# 605_motor.net
KiCad netlist of a schematic drawn in EAGLE
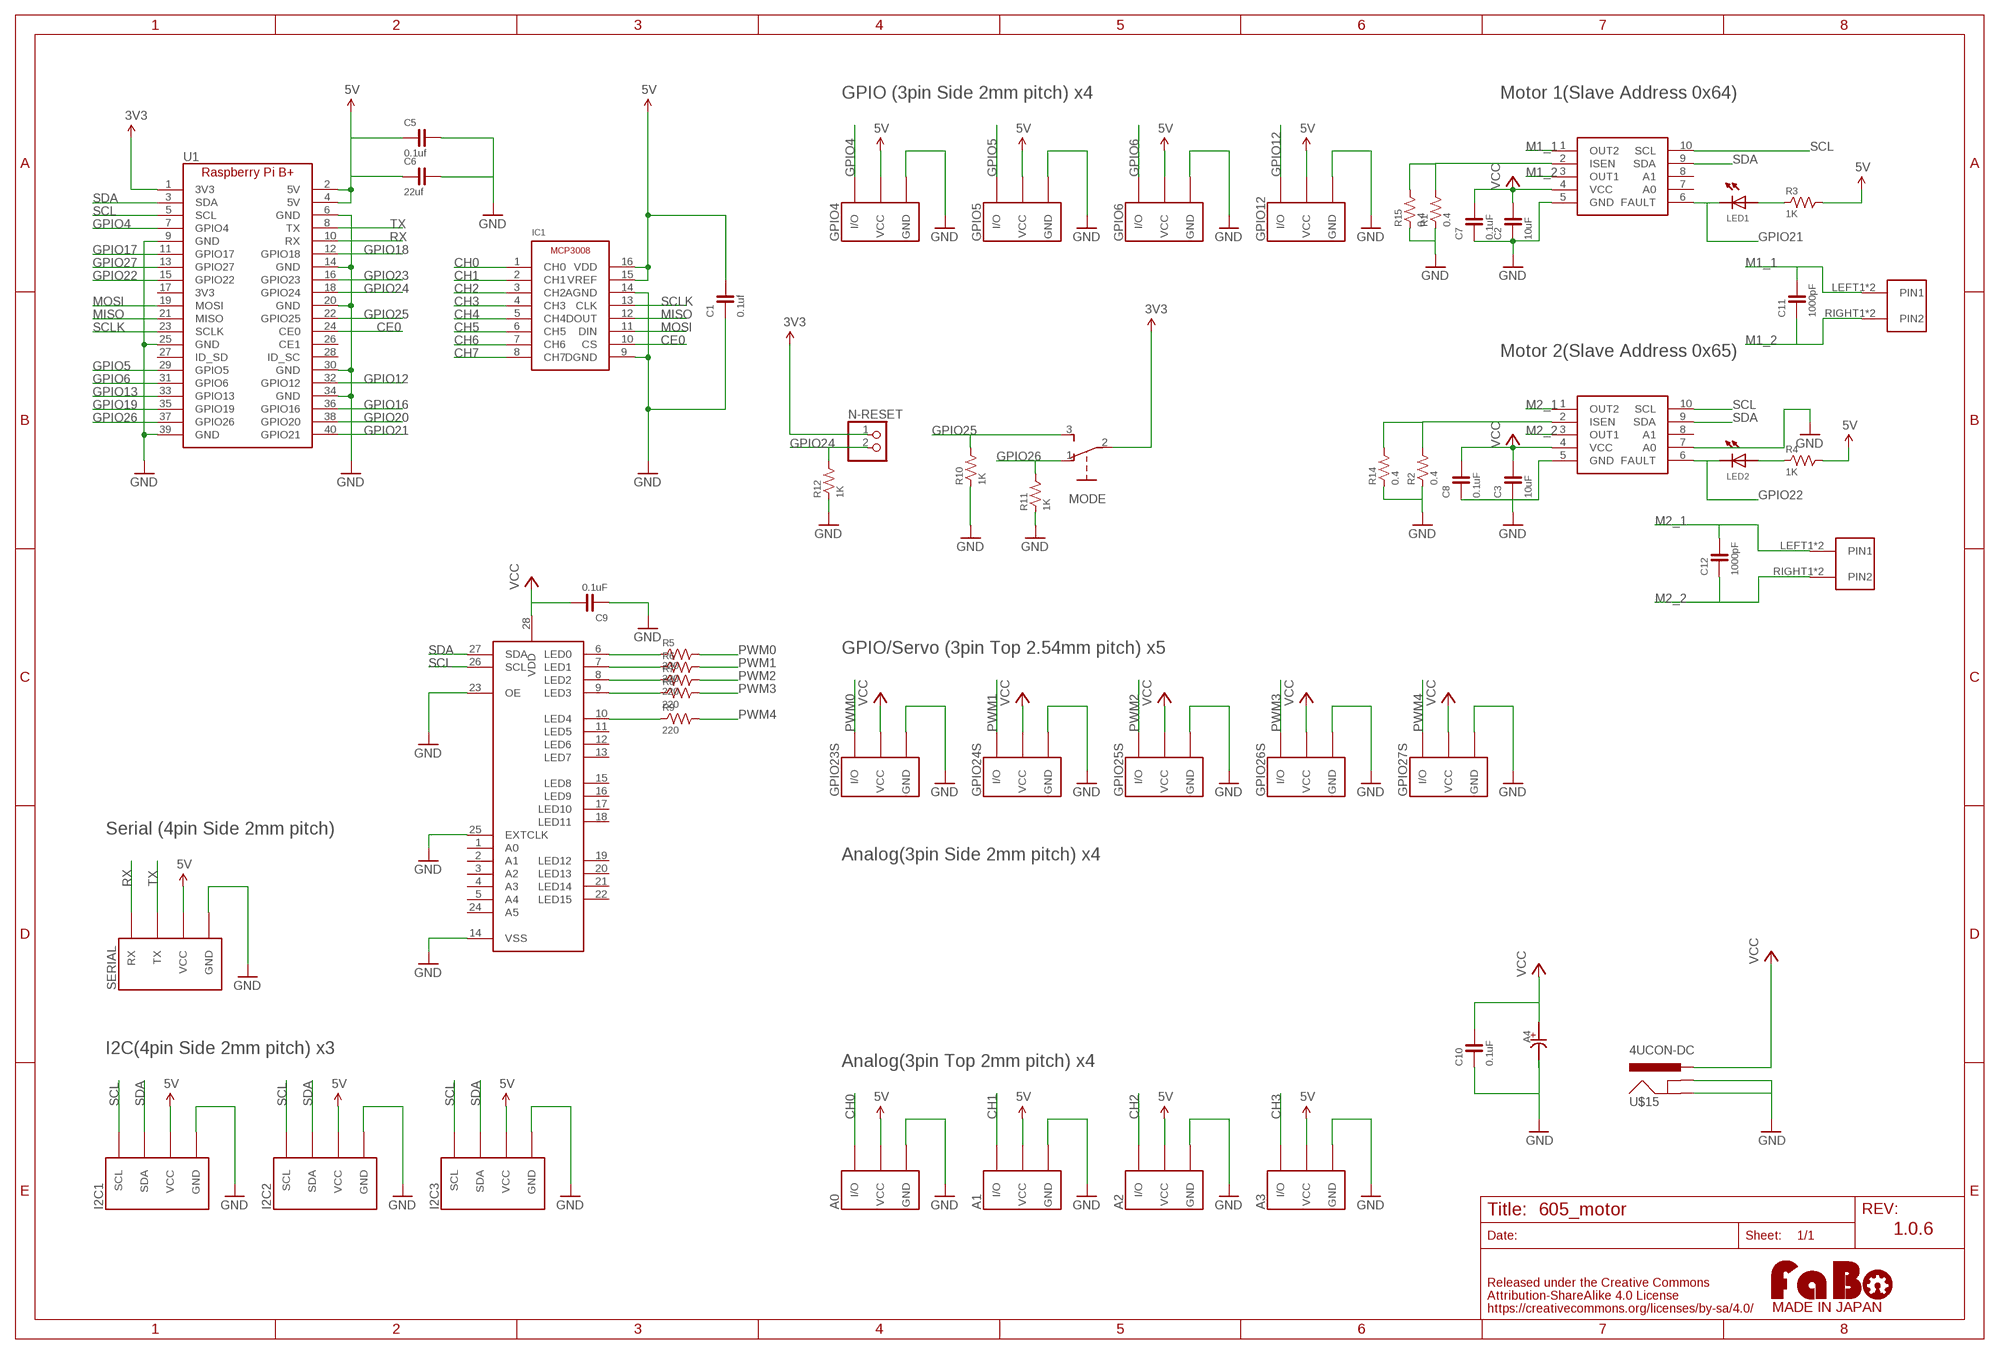
[diagram p0: schematic, sheet 1]

(export (version "E")
  (design (tool "Eeschema 10.0.6"))
  (components
    (comp (ref "A0")
      (value "FABO_BRICK_3PIN-B03B-PASK-1")
      (footprint "eagle-import:FABO_BRICK_3PIN_B03B-PASK-1")
      (libsource (lib "eagle-import") (part "FABO_BRICK_3PIN-B03B-PASK-1"))
    )
    (comp (ref "A1")
      (value "FABO_BRICK_3PIN-B03B-PASK-1")
      (footprint "eagle-import:FABO_BRICK_3PIN_B03B-PASK-1")
      (libsource (lib "eagle-import") (part "FABO_BRICK_3PIN-B03B-PASK-1"))
    )
    (comp (ref "A2")
      (value "FABO_BRICK_3PIN-B03B-PASK-1")
      (footprint "eagle-import:FABO_BRICK_3PIN_B03B-PASK-1")
      (libsource (lib "eagle-import") (part "FABO_BRICK_3PIN-B03B-PASK-1"))
    )
    (comp (ref "A3")
      (value "FABO_BRICK_3PIN-B03B-PASK-1")
      (footprint "eagle-import:FABO_BRICK_3PIN_B03B-PASK-1")
      (libsource (lib "eagle-import") (part "FABO_BRICK_3PIN-B03B-PASK-1"))
    )
    (comp (ref "A4")
      (value "CAPACITOR-ALUMIN")
      (footprint "eagle-import:H13")
      (libsource (lib "eagle-import") (part "CAPACITOR-ALUMIN"))
    )
    (comp (ref "C1")
      (value "0.1uf")
      (footprint "eagle-import:0603")
      (libsource (lib "eagle-import") (part "CAPACITOR-0603"))
    )
    (comp (ref "C2")
      (value "10uF")
      (footprint "eagle-import:0603")
      (libsource (lib "eagle-import") (part "CAPACITOR-0603"))
    )
    (comp (ref "C3")
      (value "10uF")
      (footprint "eagle-import:0603")
      (libsource (lib "eagle-import") (part "CAPACITOR-0603"))
    )
    (comp (ref "C5")
      (value "0.1uf")
      (footprint "eagle-import:0603")
      (libsource (lib "eagle-import") (part "CAPACITOR-0603"))
    )
    (comp (ref "C6")
      (value "22uf")
      (footprint "eagle-import:0603")
      (libsource (lib "eagle-import") (part "CAPACITOR-0603"))
    )
    (comp (ref "C7")
      (value "0.1uF")
      (footprint "eagle-import:0603")
      (libsource (lib "eagle-import") (part "CAPACITOR-0603"))
    )
    (comp (ref "C8")
      (value "0.1uF")
      (footprint "eagle-import:0603")
      (libsource (lib "eagle-import") (part "CAPACITOR-0603"))
    )
    (comp (ref "C9")
      (value "0.1uF")
      (footprint "eagle-import:0603")
      (libsource (lib "eagle-import") (part "CAPACITOR-0603"))
    )
    (comp (ref "C10")
      (value "0.1uF")
      (footprint "eagle-import:0603")
      (libsource (lib "eagle-import") (part "CAPACITOR-0603"))
    )
    (comp (ref "C11")
      (value "1000pF")
      (footprint "eagle-import:0603")
      (libsource (lib "eagle-import") (part "CAPACITOR-0603"))
    )
    (comp (ref "C12")
      (value "1000pF")
      (footprint "eagle-import:0603")
      (libsource (lib "eagle-import") (part "CAPACITOR-0603"))
    )
    (comp (ref "GPIO4")
      (value "FABO_BRICK_3PIN-S03B-PASK-2")
      (footprint "eagle-import:FABO_BRICK_3PIN_S03B-PASK-2")
      (libsource (lib "eagle-import") (part "FABO_BRICK_3PIN-S03B-PASK-2"))
    )
    (comp (ref "GPIO5")
      (value "FABO_BRICK_3PIN-S03B-PASK-2")
      (footprint "eagle-import:FABO_BRICK_3PIN_S03B-PASK-2")
      (libsource (lib "eagle-import") (part "FABO_BRICK_3PIN-S03B-PASK-2"))
    )
    (comp (ref "GPIO6")
      (value "FABO_BRICK_3PIN-S03B-PASK-2")
      (footprint "eagle-import:FABO_BRICK_3PIN_S03B-PASK-2")
      (libsource (lib "eagle-import") (part "FABO_BRICK_3PIN-S03B-PASK-2"))
    )
    (comp (ref "GPIO12")
      (value "FABO_BRICK_3PIN-S03B-PASK-2")
      (footprint "eagle-import:FABO_BRICK_3PIN_S03B-PASK-2")
      (libsource (lib "eagle-import") (part "FABO_BRICK_3PIN-S03B-PASK-2"))
    )
    (comp (ref "GPIO23S")
      (value "FABO_BRICK_3PIN-HEADER")
      (footprint "eagle-import:FABO_BRICK_3PIN_HEADER")
      (libsource (lib "eagle-import") (part "FABO_BRICK_3PIN-HEADER"))
    )
    (comp (ref "GPIO24S")
      (value "FABO_BRICK_3PIN-HEADER")
      (footprint "eagle-import:FABO_BRICK_3PIN_HEADER")
      (libsource (lib "eagle-import") (part "FABO_BRICK_3PIN-HEADER"))
    )
    (comp (ref "GPIO25S")
      (value "FABO_BRICK_3PIN-HEADER")
      (footprint "eagle-import:FABO_BRICK_3PIN_HEADER")
      (libsource (lib "eagle-import") (part "FABO_BRICK_3PIN-HEADER"))
    )
    (comp (ref "GPIO26S")
      (value "FABO_BRICK_3PIN-HEADER")
      (footprint "eagle-import:FABO_BRICK_3PIN_HEADER")
      (libsource (lib "eagle-import") (part "FABO_BRICK_3PIN-HEADER"))
    )
    (comp (ref "GPIO27S")
      (value "FABO_BRICK_3PIN-HEADER")
      (footprint "eagle-import:FABO_BRICK_3PIN_HEADER")
      (libsource (lib "eagle-import") (part "FABO_BRICK_3PIN-HEADER"))
    )
    (comp (ref "I2C1")
      (value "FABO_BRICK_I2C-S04B-PASK-2")
      (footprint "eagle-import:FABO_BRICK_I2C_S04B-PASK-2")
      (libsource (lib "eagle-import") (part "FABO_BRICK_I2C-S04B-PASK-2"))
    )
    (comp (ref "I2C2")
      (value "FABO_BRICK_I2C-S04B-PASK-2")
      (footprint "eagle-import:FABO_BRICK_I2C_S04B-PASK-2")
      (libsource (lib "eagle-import") (part "FABO_BRICK_I2C-S04B-PASK-2"))
    )
    (comp (ref "I2C3")
      (value "FABO_BRICK_I2C-S04B-PASK-2")
      (footprint "eagle-import:FABO_BRICK_I2C_S04B-PASK-2")
      (libsource (lib "eagle-import") (part "FABO_BRICK_I2C-S04B-PASK-2"))
    )
    (comp (ref "IC1")
      (value "MICROCHIP-MCP3008")
      (footprint "eagle-import:MICROCHIP-MCP3008")
      (libsource (lib "eagle-import") (part "MICROCHIP-MCP3008"))
    )
    (comp (ref "LED1")
      (value "LED-0603")
      (footprint "eagle-import:0603")
      (libsource (lib "eagle-import") (part "LED-0603"))
    )
    (comp (ref "LED2")
      (value "LED-0603")
      (footprint "eagle-import:0603")
      (libsource (lib "eagle-import") (part "LED-0603"))
    )
    (comp (ref "MODE")
      (value "SLIDE-EG1218")
      (footprint "eagle-import:EG1218")
      (libsource (lib "eagle-import") (part "SLIDE-EG1218"))
    )
    (comp (ref "N-RESET")
      (value "PINHD-1X2")
      (footprint "eagle-import:1X02")
      (libsource (lib "eagle-import") (part "PINHD-1X2"))
    )
    (comp (ref "R1")
      (value "0.4")
      (footprint "eagle-import:0603")
      (libsource (lib "eagle-import") (part "RESISTOR-0603"))
    )
    (comp (ref "R2")
      (value "0.4")
      (footprint "eagle-import:0603")
      (libsource (lib "eagle-import") (part "RESISTOR-0603"))
    )
    (comp (ref "R3")
      (value "1K")
      (footprint "eagle-import:0603")
      (libsource (lib "eagle-import") (part "RESISTOR-0603"))
    )
    (comp (ref "R4")
      (value "1K")
      (footprint "eagle-import:0603")
      (libsource (lib "eagle-import") (part "RESISTOR-0603"))
    )
    (comp (ref "R5")
      (value "220")
      (footprint "eagle-import:0603")
      (libsource (lib "eagle-import") (part "RESISTOR-0603"))
    )
    (comp (ref "R6")
      (value "220")
      (footprint "eagle-import:0603")
      (libsource (lib "eagle-import") (part "RESISTOR-0603"))
    )
    (comp (ref "R7")
      (value "220")
      (footprint "eagle-import:0603")
      (libsource (lib "eagle-import") (part "RESISTOR-0603"))
    )
    (comp (ref "R8")
      (value "220")
      (footprint "eagle-import:0603")
      (libsource (lib "eagle-import") (part "RESISTOR-0603"))
    )
    (comp (ref "R9")
      (value "220")
      (footprint "eagle-import:0603")
      (libsource (lib "eagle-import") (part "RESISTOR-0603"))
    )
    (comp (ref "R10")
      (value "1K")
      (footprint "eagle-import:0603")
      (libsource (lib "eagle-import") (part "RESISTOR-0603"))
    )
    (comp (ref "R11")
      (value "1K")
      (footprint "eagle-import:0603")
      (libsource (lib "eagle-import") (part "RESISTOR-0603"))
    )
    (comp (ref "R12")
      (value "1K")
      (footprint "eagle-import:0603")
      (libsource (lib "eagle-import") (part "RESISTOR-0603"))
    )
    (comp (ref "R14")
      (value "0.4")
      (footprint "eagle-import:0603")
      (libsource (lib "eagle-import") (part "RESISTOR-0603"))
    )
    (comp (ref "R15")
      (value "0.4")
      (footprint "eagle-import:0603")
      (libsource (lib "eagle-import") (part "RESISTOR-0603"))
    )
    (comp (ref "SERIAL")
      (value "FABO_BRICK_SERIAL-S04B-PASK-2")
      (footprint "eagle-import:FABO_BRICK_SERIAL_S04B-PASK-2")
      (libsource (lib "eagle-import") (part "FABO_BRICK_SERIAL-S04B-PASK-2"))
    )
    (comp (ref "U$8")
      (value "DRV8830")
      (footprint "eagle-import:DRV8830")
      (libsource (lib "eagle-import") (part "DRV8830"))
    )
    (comp (ref "U$9")
      (value "PCA9685")
      (footprint "eagle-import:PCA9685")
      (libsource (lib "eagle-import") (part "PCA9685"))
    )
    (comp (ref "U$10")
      (value "DRV8830")
      (footprint "eagle-import:DRV8830")
      (libsource (lib "eagle-import") (part "DRV8830"))
    )
    (comp (ref "U$12")
      (value "ML-1400-S1")
      (footprint "eagle-import:ML-1400-S1")
      (libsource (lib "eagle-import") (part "ML-1400-S1"))
    )
    (comp (ref "U$13")
      (value "ML-1400-S1")
      (footprint "eagle-import:ML-1400-S1")
      (libsource (lib "eagle-import") (part "ML-1400-S1"))
    )
    (comp (ref "U$14")
      (value "LOGO_FABO-M")
      (footprint "eagle-import:LOGO_FABO_MS")
      (libsource (lib "eagle-import") (part "LOGO_FABO-M"))
    )
    (comp (ref "U$15")
      (value "4UCON-DC")
      (footprint "eagle-import:4UCON-DC")
      (libsource (lib "eagle-import") (part "4UCON-DC"))
    )
    (comp (ref "U1")
      (value "RASPBERRY_PI_B+")
      (footprint "eagle-import:RASPBERRY_PI_B+")
      (libsource (lib "eagle-import") (part "RASPBERRY_PI_B+"))
    )
  )
  (nets
    (net (code "1") (name "/CE0") (class "Default")
      (node (ref "IC1") (pin "10") (pinfunction "CS_10") (pintype "bidirectional"))
      (node (ref "U1") (pin "24") (pinfunction "CE0_24") (pintype "bidirectional"))
    )
    (net (code "2") (name "/CH0") (class "Default")
      (node (ref "A0") (pin "I/O") (pinfunction "I/O_I/O") (pintype "bidirectional"))
      (node (ref "IC1") (pin "1") (pinfunction "CH0_1") (pintype "bidirectional"))
    )
    (net (code "3") (name "/CH1") (class "Default")
      (node (ref "A1") (pin "I/O") (pinfunction "I/O_I/O") (pintype "bidirectional"))
      (node (ref "IC1") (pin "2") (pinfunction "CH1_2") (pintype "bidirectional"))
    )
    (net (code "4") (name "/CH2") (class "Default")
      (node (ref "A2") (pin "I/O") (pinfunction "I/O_I/O") (pintype "bidirectional"))
      (node (ref "IC1") (pin "3") (pinfunction "CH2_3") (pintype "bidirectional"))
    )
    (net (code "5") (name "/CH3") (class "Default")
      (node (ref "A3") (pin "I/O") (pinfunction "I/O_I/O") (pintype "bidirectional"))
      (node (ref "IC1") (pin "4") (pinfunction "CH3_4") (pintype "bidirectional"))
    )
    (net (code "6") (name "/CH4") (class "Default")
      (node (ref "IC1") (pin "5") (pinfunction "CH4_5") (pintype "bidirectional"))
    )
    (net (code "7") (name "/CH5") (class "Default")
      (node (ref "IC1") (pin "6") (pinfunction "CH5_6") (pintype "bidirectional"))
    )
    (net (code "8") (name "/CH6") (class "Default")
      (node (ref "IC1") (pin "7") (pinfunction "CH6_7") (pintype "bidirectional"))
    )
    (net (code "9") (name "/CH7") (class "Default")
      (node (ref "IC1") (pin "8") (pinfunction "CH7_8") (pintype "bidirectional"))
    )
    (net (code "10") (name "/GPIO4") (class "Default")
      (node (ref "GPIO4") (pin "I/O") (pinfunction "I/O_I/O") (pintype "bidirectional"))
      (node (ref "U1") (pin "7") (pinfunction "GPIO4_7") (pintype "bidirectional"))
    )
    (net (code "11") (name "/GPIO5") (class "Default")
      (node (ref "GPIO5") (pin "I/O") (pinfunction "I/O_I/O") (pintype "bidirectional"))
      (node (ref "U1") (pin "29") (pinfunction "GPIO5_29") (pintype "bidirectional"))
    )
    (net (code "12") (name "/GPIO6") (class "Default")
      (node (ref "GPIO6") (pin "I/O") (pinfunction "I/O_I/O") (pintype "bidirectional"))
      (node (ref "U1") (pin "31") (pinfunction "GPIO6_31") (pintype "bidirectional"))
    )
    (net (code "13") (name "/GPIO12") (class "Default")
      (node (ref "GPIO12") (pin "I/O") (pinfunction "I/O_I/O") (pintype "bidirectional"))
      (node (ref "U1") (pin "32") (pinfunction "GPIO12_32") (pintype "bidirectional"))
    )
    (net (code "14") (name "/GPIO13") (class "Default")
      (node (ref "U1") (pin "33") (pinfunction "GPIO13_33") (pintype "bidirectional"))
    )
    (net (code "15") (name "/GPIO16") (class "Default")
      (node (ref "U1") (pin "36") (pinfunction "GPIO16_36") (pintype "bidirectional"))
    )
    (net (code "16") (name "/GPIO17") (class "Default")
      (node (ref "U1") (pin "11") (pinfunction "GPIO17_11") (pintype "bidirectional"))
    )
    (net (code "17") (name "/GPIO18") (class "Default")
      (node (ref "U1") (pin "12") (pinfunction "GPIO18_12") (pintype "bidirectional"))
    )
    (net (code "18") (name "/GPIO19") (class "Default")
      (node (ref "U1") (pin "35") (pinfunction "GPIO19_35") (pintype "bidirectional"))
    )
    (net (code "19") (name "/GPIO20") (class "Default")
      (node (ref "U1") (pin "38") (pinfunction "GPIO20_38") (pintype "bidirectional"))
    )
    (net (code "20") (name "/GPIO21") (class "Default")
      (node (ref "LED1") (pin "CATHODE") (pinfunction "CATHODE_CATHODE") (pintype "passive"))
      (node (ref "U$8") (pin "6") (pinfunction "FAULT_6") (pintype "bidirectional"))
      (node (ref "U1") (pin "40") (pinfunction "GPIO21_40") (pintype "bidirectional"))
    )
    (net (code "21") (name "/GPIO22") (class "Default")
      (node (ref "LED2") (pin "CATHODE") (pinfunction "CATHODE_CATHODE") (pintype "passive"))
      (node (ref "U$10") (pin "6") (pinfunction "FAULT_6") (pintype "bidirectional"))
      (node (ref "U1") (pin "15") (pinfunction "GPIO22_15") (pintype "bidirectional"))
    )
    (net (code "22") (name "/GPIO23") (class "Default")
      (node (ref "U1") (pin "16") (pinfunction "GPIO23_16") (pintype "bidirectional"))
    )
    (net (code "23") (name "/GPIO24") (class "Default")
      (node (ref "N-RESET") (pin "2") (pinfunction "2_2") (pintype "passive"))
      (node (ref "R12") (pin "2") (pinfunction "2_2") (pintype "bidirectional"))
      (node (ref "U1") (pin "18") (pinfunction "GPIO24_18") (pintype "bidirectional"))
    )
    (net (code "24") (name "/GPIO25") (class "Default")
      (node (ref "MODE") (pin "3") (pinfunction "3_3") (pintype "passive"))
      (node (ref "R10") (pin "2") (pinfunction "2_2") (pintype "bidirectional"))
      (node (ref "U1") (pin "22") (pinfunction "GPIO25_22") (pintype "bidirectional"))
    )
    (net (code "25") (name "/GPIO26") (class "Default")
      (node (ref "MODE") (pin "1") (pinfunction "1_1") (pintype "passive"))
      (node (ref "R11") (pin "2") (pinfunction "2_2") (pintype "bidirectional"))
      (node (ref "U1") (pin "37") (pinfunction "GPIO26_37") (pintype "bidirectional"))
    )
    (net (code "26") (name "/GPIO27") (class "Default")
      (node (ref "U1") (pin "13") (pinfunction "GPIO27_13") (pintype "bidirectional"))
    )
    (net (code "27") (name "/M1_1") (class "Default")
      (node (ref "C11") (pin "2") (pinfunction "2_2") (pintype "passive"))
      (node (ref "U$12") (pin "LEFT1") (pinfunction "PIN1_LEFT1") (pintype "bidirectional"))
      (node (ref "U$12") (pin "LEFT2") (pinfunction "PIN1_LEFT2") (pintype "bidirectional"))
      (node (ref "U$8") (pin "1") (pinfunction "OUT2_1") (pintype "bidirectional"))
    )
    (net (code "28") (name "/M1_2") (class "Default")
      (node (ref "C11") (pin "1") (pinfunction "1_1") (pintype "passive"))
      (node (ref "U$12") (pin "RIGHT1") (pinfunction "PIN2_RIGHT1") (pintype "bidirectional"))
      (node (ref "U$12") (pin "RIGHT2") (pinfunction "PIN2_RIGHT2") (pintype "bidirectional"))
      (node (ref "U$8") (pin "3") (pinfunction "OUT1_3") (pintype "bidirectional"))
    )
    (net (code "29") (name "/M2_1") (class "Default")
      (node (ref "C12") (pin "2") (pinfunction "2_2") (pintype "passive"))
      (node (ref "U$10") (pin "1") (pinfunction "OUT2_1") (pintype "bidirectional"))
      (node (ref "U$13") (pin "LEFT1") (pinfunction "PIN1_LEFT1") (pintype "bidirectional"))
      (node (ref "U$13") (pin "LEFT2") (pinfunction "PIN1_LEFT2") (pintype "bidirectional"))
    )
    (net (code "30") (name "/M2_2") (class "Default")
      (node (ref "C12") (pin "1") (pinfunction "1_1") (pintype "passive"))
      (node (ref "U$10") (pin "3") (pinfunction "OUT1_3") (pintype "bidirectional"))
      (node (ref "U$13") (pin "RIGHT1") (pinfunction "PIN2_RIGHT1") (pintype "bidirectional"))
      (node (ref "U$13") (pin "RIGHT2") (pinfunction "PIN2_RIGHT2") (pintype "bidirectional"))
    )
    (net (code "31") (name "/MISO") (class "Default")
      (node (ref "IC1") (pin "12") (pinfunction "DOUT_12") (pintype "bidirectional"))
      (node (ref "U1") (pin "21") (pinfunction "MISO_21") (pintype "bidirectional"))
    )
    (net (code "32") (name "/MOSI") (class "Default")
      (node (ref "IC1") (pin "11") (pinfunction "DIN_11") (pintype "bidirectional"))
      (node (ref "U1") (pin "19") (pinfunction "MOSI_19") (pintype "bidirectional"))
    )
    (net (code "33") (name "/PWM0") (class "Default")
      (node (ref "GPIO23S") (pin "I/O") (pinfunction "I/O_I/O") (pintype "bidirectional"))
      (node (ref "R5") (pin "2") (pinfunction "2_2") (pintype "bidirectional"))
    )
    (net (code "34") (name "/PWM1") (class "Default")
      (node (ref "GPIO24S") (pin "I/O") (pinfunction "I/O_I/O") (pintype "bidirectional"))
      (node (ref "R6") (pin "2") (pinfunction "2_2") (pintype "bidirectional"))
    )
    (net (code "35") (name "/PWM2") (class "Default")
      (node (ref "GPIO25S") (pin "I/O") (pinfunction "I/O_I/O") (pintype "bidirectional"))
      (node (ref "R7") (pin "2") (pinfunction "2_2") (pintype "bidirectional"))
    )
    (net (code "36") (name "/PWM3") (class "Default")
      (node (ref "GPIO26S") (pin "I/O") (pinfunction "I/O_I/O") (pintype "bidirectional"))
      (node (ref "R8") (pin "2") (pinfunction "2_2") (pintype "bidirectional"))
    )
    (net (code "37") (name "/PWM4") (class "Default")
      (node (ref "GPIO27S") (pin "I/O") (pinfunction "I/O_I/O") (pintype "bidirectional"))
      (node (ref "R9") (pin "2") (pinfunction "2_2") (pintype "bidirectional"))
    )
    (net (code "38") (name "/RX") (class "Default")
      (node (ref "SERIAL") (pin "RX") (pinfunction "RX_RX") (pintype "bidirectional"))
      (node (ref "U1") (pin "10") (pinfunction "RX_10") (pintype "bidirectional"))
    )
    (net (code "39") (name "/SCL") (class "Default")
      (node (ref "I2C1") (pin "SCL") (pinfunction "SCL_SCL") (pintype "bidirectional"))
      (node (ref "I2C2") (pin "SCL") (pinfunction "SCL_SCL") (pintype "bidirectional"))
      (node (ref "I2C3") (pin "SCL") (pinfunction "SCL_SCL") (pintype "bidirectional"))
      (node (ref "U$10") (pin "10") (pinfunction "SCL_10") (pintype "bidirectional"))
      (node (ref "U$8") (pin "10") (pinfunction "SCL_10") (pintype "bidirectional"))
      (node (ref "U$9") (pin "26") (pinfunction "SCL_26") (pintype "bidirectional"))
      (node (ref "U1") (pin "5") (pinfunction "SCL_5") (pintype "bidirectional"))
    )
    (net (code "40") (name "/SCLK") (class "Default")
      (node (ref "IC1") (pin "13") (pinfunction "CLK_13") (pintype "bidirectional"))
      (node (ref "U1") (pin "23") (pinfunction "SCLK_23") (pintype "bidirectional"))
    )
    (net (code "41") (name "/SDA") (class "Default")
      (node (ref "I2C1") (pin "SDA") (pinfunction "SDA_SDA") (pintype "bidirectional"))
      (node (ref "I2C2") (pin "SDA") (pinfunction "SDA_SDA") (pintype "bidirectional"))
      (node (ref "I2C3") (pin "SDA") (pinfunction "SDA_SDA") (pintype "bidirectional"))
      (node (ref "U$10") (pin "9") (pinfunction "SDA_9") (pintype "bidirectional"))
      (node (ref "U$8") (pin "9") (pinfunction "SDA_9") (pintype "bidirectional"))
      (node (ref "U$9") (pin "27") (pinfunction "SDA_27") (pintype "bidirectional"))
      (node (ref "U1") (pin "3") (pinfunction "SDA_3") (pintype "bidirectional"))
    )
    (net (code "42") (name "/TX") (class "Default")
      (node (ref "SERIAL") (pin "TX") (pinfunction "TX_TX") (pintype "bidirectional"))
      (node (ref "U1") (pin "8") (pinfunction "TX_8") (pintype "bidirectional"))
    )
    (net (code "43") (name "3V3") (class "Default")
      (node (ref "MODE") (pin "2") (pinfunction "2_2") (pintype "passive"))
      (node (ref "N-RESET") (pin "1") (pinfunction "1_1") (pintype "passive"))
      (node (ref "U1") (pin "1") (pinfunction "3V3_1") (pintype "bidirectional"))
    )
    (net (code "44") (name "5V") (class "Default")
      (node (ref "A0") (pin "VCC") (pinfunction "VCC_VCC") (pintype "bidirectional"))
      (node (ref "A1") (pin "VCC") (pinfunction "VCC_VCC") (pintype "bidirectional"))
      (node (ref "A2") (pin "VCC") (pinfunction "VCC_VCC") (pintype "bidirectional"))
      (node (ref "A3") (pin "VCC") (pinfunction "VCC_VCC") (pintype "bidirectional"))
      (node (ref "C1") (pin "2") (pinfunction "2_2") (pintype "passive"))
      (node (ref "C5") (pin "1") (pinfunction "1_1") (pintype "passive"))
      (node (ref "C6") (pin "1") (pinfunction "1_1") (pintype "passive"))
      (node (ref "GPIO12") (pin "VCC") (pinfunction "VCC_VCC") (pintype "bidirectional"))
      (node (ref "GPIO4") (pin "VCC") (pinfunction "VCC_VCC") (pintype "bidirectional"))
      (node (ref "GPIO5") (pin "VCC") (pinfunction "VCC_VCC") (pintype "bidirectional"))
      (node (ref "GPIO6") (pin "VCC") (pinfunction "VCC_VCC") (pintype "bidirectional"))
      (node (ref "I2C1") (pin "VCC") (pinfunction "VCC_VCC") (pintype "bidirectional"))
      (node (ref "I2C2") (pin "VCC") (pinfunction "VCC_VCC") (pintype "bidirectional"))
      (node (ref "I2C3") (pin "VCC") (pinfunction "VCC_VCC") (pintype "bidirectional"))
      (node (ref "IC1") (pin "15") (pinfunction "VREF_15") (pintype "bidirectional"))
      (node (ref "IC1") (pin "16") (pinfunction "VDD_16") (pintype "bidirectional"))
      (node (ref "R3") (pin "2") (pinfunction "2_2") (pintype "bidirectional"))
      (node (ref "R4") (pin "2") (pinfunction "2_2") (pintype "bidirectional"))
      (node (ref "SERIAL") (pin "VCC") (pinfunction "VCC_VCC") (pintype "bidirectional"))
      (node (ref "U1") (pin "2") (pinfunction "5V_2") (pintype "bidirectional"))
      (node (ref "U1") (pin "4") (pinfunction "5V_4") (pintype "bidirectional"))
    )
    (net (code "45") (name "GND") (class "Default")
      (node (ref "A0") (pin "GND") (pinfunction "GND_GND") (pintype "bidirectional"))
      (node (ref "A1") (pin "GND") (pinfunction "GND_GND") (pintype "bidirectional"))
      (node (ref "A2") (pin "GND") (pinfunction "GND_GND") (pintype "bidirectional"))
      (node (ref "A3") (pin "GND") (pinfunction "GND_GND") (pintype "bidirectional"))
      (node (ref "A4") (pin "MINUS") (pinfunction "-_MINUS") (pintype "passive"))
      (node (ref "C1") (pin "1") (pinfunction "1_1") (pintype "passive"))
      (node (ref "C10") (pin "1") (pinfunction "1_1") (pintype "passive"))
      (node (ref "C2") (pin "1") (pinfunction "1_1") (pintype "passive"))
      (node (ref "C3") (pin "1") (pinfunction "1_1") (pintype "passive"))
      (node (ref "C5") (pin "2") (pinfunction "2_2") (pintype "passive"))
      (node (ref "C6") (pin "2") (pinfunction "2_2") (pintype "passive"))
      (node (ref "C7") (pin "1") (pinfunction "1_1") (pintype "passive"))
      (node (ref "C8") (pin "1") (pinfunction "1_1") (pintype "passive"))
      (node (ref "C9") (pin "1") (pinfunction "1_1") (pintype "passive"))
      (node (ref "GPIO12") (pin "GND") (pinfunction "GND_GND") (pintype "bidirectional"))
      (node (ref "GPIO23S") (pin "GND") (pinfunction "GND_GND") (pintype "bidirectional"))
      (node (ref "GPIO24S") (pin "GND") (pinfunction "GND_GND") (pintype "bidirectional"))
      (node (ref "GPIO25S") (pin "GND") (pinfunction "GND_GND") (pintype "bidirectional"))
      (node (ref "GPIO26S") (pin "GND") (pinfunction "GND_GND") (pintype "bidirectional"))
      (node (ref "GPIO27S") (pin "GND") (pinfunction "GND_GND") (pintype "bidirectional"))
      (node (ref "GPIO4") (pin "GND") (pinfunction "GND_GND") (pintype "bidirectional"))
      (node (ref "GPIO5") (pin "GND") (pinfunction "GND_GND") (pintype "bidirectional"))
      (node (ref "GPIO6") (pin "GND") (pinfunction "GND_GND") (pintype "bidirectional"))
      (node (ref "I2C1") (pin "GND") (pinfunction "GND_GND") (pintype "bidirectional"))
      (node (ref "I2C2") (pin "GND") (pinfunction "GND_GND") (pintype "bidirectional"))
      (node (ref "I2C3") (pin "GND") (pinfunction "GND_GND") (pintype "bidirectional"))
      (node (ref "IC1") (pin "14") (pinfunction "AGND_14") (pintype "bidirectional"))
      (node (ref "IC1") (pin "9") (pinfunction "DGND_9") (pintype "bidirectional"))
      (node (ref "R1") (pin "1") (pinfunction "1_1") (pintype "bidirectional"))
      (node (ref "R10") (pin "1") (pinfunction "1_1") (pintype "bidirectional"))
      (node (ref "R11") (pin "1") (pinfunction "1_1") (pintype "bidirectional"))
      (node (ref "R12") (pin "1") (pinfunction "1_1") (pintype "bidirectional"))
      (node (ref "R14") (pin "1") (pinfunction "1_1") (pintype "bidirectional"))
      (node (ref "R15") (pin "1") (pinfunction "1_1") (pintype "bidirectional"))
      (node (ref "R2") (pin "1") (pinfunction "1_1") (pintype "bidirectional"))
      (node (ref "SERIAL") (pin "GND") (pinfunction "GND_GND") (pintype "bidirectional"))
      (node (ref "U$10") (pin "5") (pinfunction "GND_5") (pintype "bidirectional"))
      (node (ref "U$10") (pin "7") (pinfunction "A0_7") (pintype "bidirectional"))
      (node (ref "U$15") (pin "GND1") (pinfunction "GND_GND1") (pintype "bidirectional"))
      (node (ref "U$15") (pin "GND2") (pinfunction "GNDBREAK_GND2") (pintype "bidirectional"))
      (node (ref "U$8") (pin "5") (pinfunction "GND_5") (pintype "bidirectional"))
      (node (ref "U$9") (pin "14") (pinfunction "VSS_14") (pintype "bidirectional"))
      (node (ref "U$9") (pin "23") (pinfunction "OE_23") (pintype "bidirectional"))
      (node (ref "U$9") (pin "25") (pinfunction "EXTCLK_25") (pintype "bidirectional"))
      (node (ref "U1") (pin "14") (pinfunction "GND_14") (pintype "bidirectional"))
      (node (ref "U1") (pin "20") (pinfunction "GND_20") (pintype "bidirectional"))
      (node (ref "U1") (pin "25") (pinfunction "GND_25") (pintype "bidirectional"))
      (node (ref "U1") (pin "30") (pinfunction "GND_30") (pintype "bidirectional"))
      (node (ref "U1") (pin "34") (pinfunction "GND_34") (pintype "bidirectional"))
      (node (ref "U1") (pin "39") (pinfunction "GND_39") (pintype "bidirectional"))
      (node (ref "U1") (pin "6") (pinfunction "GND_6") (pintype "bidirectional"))
      (node (ref "U1") (pin "9") (pinfunction "GND_9") (pintype "bidirectional"))
    )
    (net (code "46") (name "Net-(LED1-PadANODE)") (class "Default")
      (node (ref "LED1") (pin "ANODE") (pinfunction "ANODE_ANODE") (pintype "passive"))
      (node (ref "R3") (pin "1") (pinfunction "1_1") (pintype "bidirectional"))
    )
    (net (code "47") (name "Net-(LED2-PadANODE)") (class "Default")
      (node (ref "LED2") (pin "ANODE") (pinfunction "ANODE_ANODE") (pintype "passive"))
      (node (ref "R4") (pin "1") (pinfunction "1_1") (pintype "bidirectional"))
    )
    (net (code "48") (name "Net-(U$8-ISEN)") (class "Default")
      (node (ref "R1") (pin "2") (pinfunction "2_2") (pintype "bidirectional"))
      (node (ref "R15") (pin "2") (pinfunction "2_2") (pintype "bidirectional"))
      (node (ref "U$8") (pin "2") (pinfunction "ISEN_2") (pintype "bidirectional"))
    )
    (net (code "49") (name "Net-(U$9-LED0)") (class "Default")
      (node (ref "R5") (pin "1") (pinfunction "1_1") (pintype "bidirectional"))
      (node (ref "U$9") (pin "6") (pinfunction "LED0_6") (pintype "bidirectional"))
    )
    (net (code "50") (name "Net-(U$9-LED1)") (class "Default")
      (node (ref "R6") (pin "1") (pinfunction "1_1") (pintype "bidirectional"))
      (node (ref "U$9") (pin "7") (pinfunction "LED1_7") (pintype "bidirectional"))
    )
    (net (code "51") (name "Net-(U$9-LED2)") (class "Default")
      (node (ref "R7") (pin "1") (pinfunction "1_1") (pintype "bidirectional"))
      (node (ref "U$9") (pin "8") (pinfunction "LED2_8") (pintype "bidirectional"))
    )
    (net (code "52") (name "Net-(U$9-LED3)") (class "Default")
      (node (ref "R8") (pin "1") (pinfunction "1_1") (pintype "bidirectional"))
      (node (ref "U$9") (pin "9") (pinfunction "LED3_9") (pintype "bidirectional"))
    )
    (net (code "53") (name "Net-(U$9-LED4)") (class "Default")
      (node (ref "R9") (pin "1") (pinfunction "1_1") (pintype "bidirectional"))
      (node (ref "U$9") (pin "10") (pinfunction "LED4_10") (pintype "bidirectional"))
    )
    (net (code "54") (name "Net-(U$10-ISEN)") (class "Default")
      (node (ref "R14") (pin "2") (pinfunction "2_2") (pintype "bidirectional"))
      (node (ref "R2") (pin "2") (pinfunction "2_2") (pintype "bidirectional"))
      (node (ref "U$10") (pin "2") (pinfunction "ISEN_2") (pintype "bidirectional"))
    )
    (net (code "55") (name "VCC") (class "Default")
      (node (ref "A4") (pin "PLUS") (pinfunction "+_PLUS") (pintype "passive"))
      (node (ref "C10") (pin "2") (pinfunction "2_2") (pintype "passive"))
      (node (ref "C2") (pin "2") (pinfunction "2_2") (pintype "passive"))
      (node (ref "C3") (pin "2") (pinfunction "2_2") (pintype "passive"))
      (node (ref "C7") (pin "2") (pinfunction "2_2") (pintype "passive"))
      (node (ref "C8") (pin "2") (pinfunction "2_2") (pintype "passive"))
      (node (ref "C9") (pin "2") (pinfunction "2_2") (pintype "passive"))
      (node (ref "GPIO23S") (pin "VCC") (pinfunction "VCC_VCC") (pintype "bidirectional"))
      (node (ref "GPIO24S") (pin "VCC") (pinfunction "VCC_VCC") (pintype "bidirectional"))
      (node (ref "GPIO25S") (pin "VCC") (pinfunction "VCC_VCC") (pintype "bidirectional"))
      (node (ref "GPIO26S") (pin "VCC") (pinfunction "VCC_VCC") (pintype "bidirectional"))
      (node (ref "GPIO27S") (pin "VCC") (pinfunction "VCC_VCC") (pintype "bidirectional"))
      (node (ref "U$10") (pin "4") (pinfunction "VCC_4") (pintype "bidirectional"))
      (node (ref "U$15") (pin "VCC") (pinfunction "PWR_VCC") (pintype "bidirectional"))
      (node (ref "U$8") (pin "4") (pinfunction "VCC_4") (pintype "bidirectional"))
      (node (ref "U$9") (pin "28") (pinfunction "VDD_28") (pintype "bidirectional"))
    )
    (net (code "56") (name "unconnected-(U$8-A0-Pad7)") (class "Default")
      (node (ref "U$8") (pin "7") (pinfunction "A0_7") (pintype "bidirectional"))
    )
    (net (code "57") (name "unconnected-(U$8-A1-Pad8)") (class "Default")
      (node (ref "U$8") (pin "8") (pinfunction "A1_8") (pintype "bidirectional"))
    )
    (net (code "58") (name "unconnected-(U$9-A0-Pad1)") (class "Default")
      (node (ref "U$9") (pin "1") (pinfunction "A0_1") (pintype "bidirectional"))
    )
    (net (code "59") (name "unconnected-(U$9-A1-Pad2)") (class "Default")
      (node (ref "U$9") (pin "2") (pinfunction "A1_2") (pintype "bidirectional"))
    )
    (net (code "60") (name "unconnected-(U$9-A2-Pad3)") (class "Default")
      (node (ref "U$9") (pin "3") (pinfunction "A2_3") (pintype "bidirectional"))
    )
    (net (code "61") (name "unconnected-(U$9-A3-Pad4)") (class "Default")
      (node (ref "U$9") (pin "4") (pinfunction "A3_4") (pintype "bidirectional"))
    )
    (net (code "62") (name "unconnected-(U$9-A4-Pad5)") (class "Default")
      (node (ref "U$9") (pin "5") (pinfunction "A4_5") (pintype "bidirectional"))
    )
    (net (code "63") (name "unconnected-(U$9-A5-Pad24)") (class "Default")
      (node (ref "U$9") (pin "24") (pinfunction "A5_24") (pintype "bidirectional"))
    )
    (net (code "64") (name "unconnected-(U$9-LED5-Pad11)") (class "Default")
      (node (ref "U$9") (pin "11") (pinfunction "LED5_11") (pintype "bidirectional"))
    )
    (net (code "65") (name "unconnected-(U$9-LED6-Pad12)") (class "Default")
      (node (ref "U$9") (pin "12") (pinfunction "LED6_12") (pintype "bidirectional"))
    )
    (net (code "66") (name "unconnected-(U$9-LED7-Pad13)") (class "Default")
      (node (ref "U$9") (pin "13") (pinfunction "LED7_13") (pintype "bidirectional"))
    )
    (net (code "67") (name "unconnected-(U$9-LED8-Pad15)") (class "Default")
      (node (ref "U$9") (pin "15") (pinfunction "LED8_15") (pintype "bidirectional"))
    )
    (net (code "68") (name "unconnected-(U$9-LED9-Pad16)") (class "Default")
      (node (ref "U$9") (pin "16") (pinfunction "LED9_16") (pintype "bidirectional"))
    )
    (net (code "69") (name "unconnected-(U$9-LED10-Pad17)") (class "Default")
      (node (ref "U$9") (pin "17") (pinfunction "LED10_17") (pintype "bidirectional"))
    )
    (net (code "70") (name "unconnected-(U$9-LED11-Pad18)") (class "Default")
      (node (ref "U$9") (pin "18") (pinfunction "LED11_18") (pintype "bidirectional"))
    )
    (net (code "71") (name "unconnected-(U$9-LED12-Pad19)") (class "Default")
      (node (ref "U$9") (pin "19") (pinfunction "LED12_19") (pintype "bidirectional"))
    )
    (net (code "72") (name "unconnected-(U$9-LED13-Pad20)") (class "Default")
      (node (ref "U$9") (pin "20") (pinfunction "LED13_20") (pintype "bidirectional"))
    )
    (net (code "73") (name "unconnected-(U$9-LED14-Pad21)") (class "Default")
      (node (ref "U$9") (pin "21") (pinfunction "LED14_21") (pintype "bidirectional"))
    )
    (net (code "74") (name "unconnected-(U$9-LED15-Pad22)") (class "Default")
      (node (ref "U$9") (pin "22") (pinfunction "LED15_22") (pintype "bidirectional"))
    )
    (net (code "75") (name "unconnected-(U$10-A1-Pad8)") (class "Default")
      (node (ref "U$10") (pin "8") (pinfunction "A1_8") (pintype "bidirectional"))
    )
    (net (code "76") (name "unconnected-(U1-3V3-Pad17)") (class "Default")
      (node (ref "U1") (pin "17") (pinfunction "3V3_17") (pintype "bidirectional"))
    )
    (net (code "77") (name "unconnected-(U1-CE1-Pad26)") (class "Default")
      (node (ref "U1") (pin "26") (pinfunction "CE1_26") (pintype "bidirectional"))
    )
    (net (code "78") (name "unconnected-(U1-ID_SC-Pad28)") (class "Default")
      (node (ref "U1") (pin "28") (pinfunction "ID_SC_28") (pintype "bidirectional"))
    )
    (net (code "79") (name "unconnected-(U1-ID_SD-Pad27)") (class "Default")
      (node (ref "U1") (pin "27") (pinfunction "ID_SD_27") (pintype "bidirectional"))
    )
  )
)
